# 03-key_led_swd.net
KiCad netlist of a schematic drawn in Altium Designer
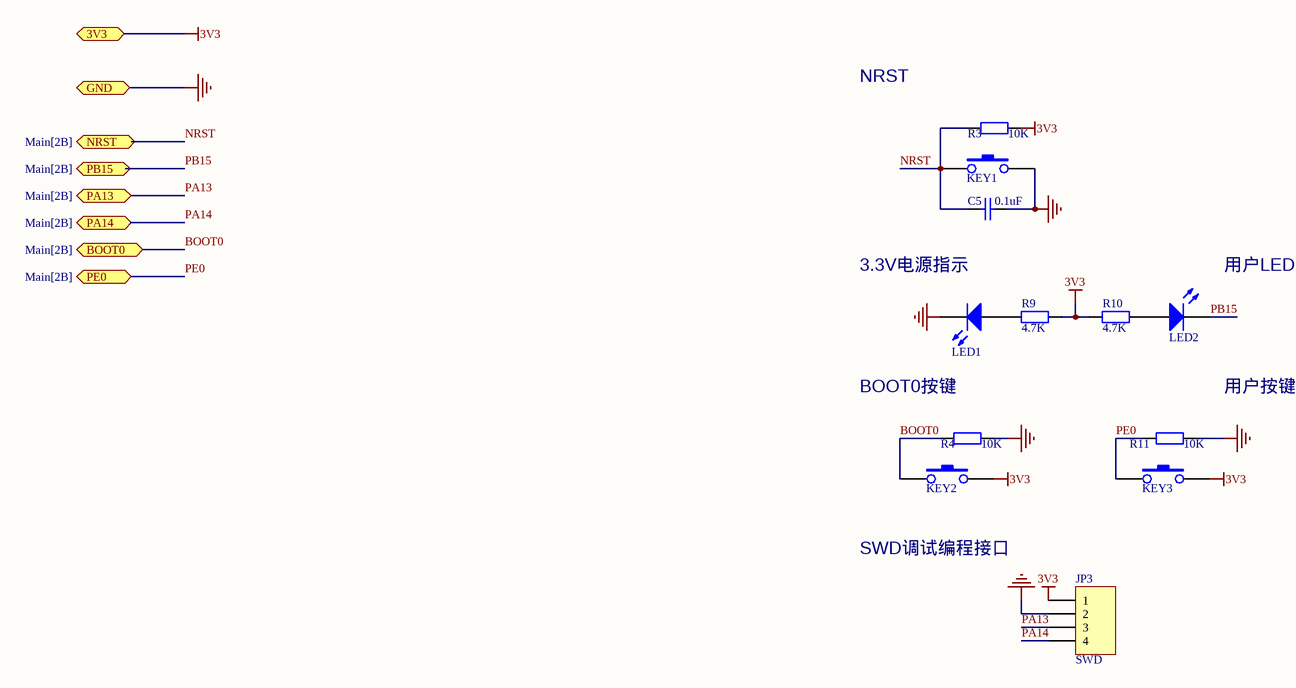
[diagram p0: 03-key+led+swd.SchDoc]

(export (version "E")
  (design (tool "Eeschema 10.0.6"))
  (components
    (comp (ref "C5") (value "0.1uF") (footprint "C 0402_L") (libsource (lib "Schlib1") (part "Cap")))
    (comp (ref "JP3")
      (value "SWD")
      (footprint "HDR2.54-WS-4P")
      (fields (field (name "PUBLISHER") "Altium Limited"))
      (libsource (lib "Schlib1") (part "Header 1*4"))
    )
    (comp (ref "KEY1") (value "KEY") (footprint "SWT3*4") (libsource (lib "Schlib1") (part "KEY")))
    (comp (ref "KEY2") (value "KEY") (footprint "SWT3*4") (libsource (lib "Schlib1") (part "KEY")))
    (comp (ref "KEY3") (value "KEY") (footprint "SWT3*4") (libsource (lib "Schlib1") (part "KEY")))
    (comp (ref "LED1") (value "LED") (footprint "LED 0603") (libsource (lib "Schlib1") (part "LED")))
    (comp (ref "LED2") (value "LED") (footprint "LED 0603") (libsource (lib "Schlib1") (part "LED")))
    (comp (ref "R3") (value "10K") (footprint "R 0402_L") (libsource (lib "Schlib1") (part "Res")))
    (comp (ref "R4") (value "10K") (footprint "R 0402_L") (libsource (lib "Schlib1") (part "Res")))
    (comp (ref "R9") (value "4.7K") (footprint "R 0402_L") (libsource (lib "Schlib1") (part "Res")))
    (comp (ref "R10") (value "4.7K") (footprint "R 0402_L") (libsource (lib "") (part "Res_1")))
    (comp (ref "R11") (value "10K") (footprint "R 0402_L") (libsource (lib "Schlib1") (part "Res")))
  )
  (nets
    (net (code "1") (name "/BOOT0") (class "Default")
      (node (ref "KEY2") (pin "1") (pinfunction "1_1") (pintype "passive"))
      (node (ref "R4") (pin "2") (pinfunction "2_2") (pintype "passive"))
    )
    (net (code "2") (name "/NRST") (class "Default")
      (node (ref "C5") (pin "2") (pinfunction "2_2") (pintype "passive"))
      (node (ref "KEY1") (pin "1") (pinfunction "1_1") (pintype "passive"))
      (node (ref "R3") (pin "2") (pinfunction "2_2") (pintype "passive"))
    )
    (net (code "3") (name "/PA13") (class "Default")
      (node (ref "JP3") (pin "3") (pinfunction "3_3") (pintype "passive"))
    )
    (net (code "4") (name "/PA14") (class "Default")
      (node (ref "JP3") (pin "4") (pinfunction "4_4") (pintype "passive"))
    )
    (net (code "5") (name "/PB15") (class "Default")
      (node (ref "LED2") (pin "2") (pinfunction "K_2") (pintype "passive"))
    )
    (net (code "6") (name "/PE0") (class "Default")
      (node (ref "KEY3") (pin "1") (pinfunction "1_1") (pintype "passive"))
      (node (ref "R11") (pin "2") (pinfunction "2_2") (pintype "passive"))
    )
    (net (code "7") (name "3V3") (class "Default")
      (node (ref "JP3") (pin "1") (pinfunction "1_1") (pintype "passive"))
      (node (ref "KEY2") (pin "2") (pinfunction "2_2") (pintype "passive"))
      (node (ref "KEY3") (pin "2") (pinfunction "2_2") (pintype "passive"))
      (node (ref "R10") (pin "1") (pinfunction "1_1") (pintype "passive"))
      (node (ref "R3") (pin "1") (pinfunction "1_1") (pintype "passive"))
      (node (ref "R9") (pin "1") (pinfunction "1_1") (pintype "passive"))
    )
    (net (code "8") (name "GND") (class "Default")
      (node (ref "C5") (pin "1") (pinfunction "1_1") (pintype "passive"))
      (node (ref "JP3") (pin "2") (pinfunction "2_2") (pintype "passive"))
      (node (ref "KEY1") (pin "2") (pinfunction "2_2") (pintype "passive"))
      (node (ref "LED1") (pin "2") (pinfunction "K_2") (pintype "passive"))
      (node (ref "R11") (pin "1") (pinfunction "1_1") (pintype "passive"))
      (node (ref "R4") (pin "1") (pinfunction "1_1") (pintype "passive"))
    )
    (net (code "9") (name "Net-(LED1-A)") (class "Default")
      (node (ref "LED1") (pin "1") (pinfunction "A_1") (pintype "passive"))
      (node (ref "R9") (pin "2") (pinfunction "2_2") (pintype "passive"))
    )
    (net (code "10") (name "Net-(LED2-A)") (class "Default")
      (node (ref "LED2") (pin "1") (pinfunction "A_1") (pintype "passive"))
      (node (ref "R10") (pin "2") (pinfunction "2_2") (pintype "passive"))
    )
  )
)
